# usb_2_0.net
KiCad netlist of a schematic drawn in Altium Designer
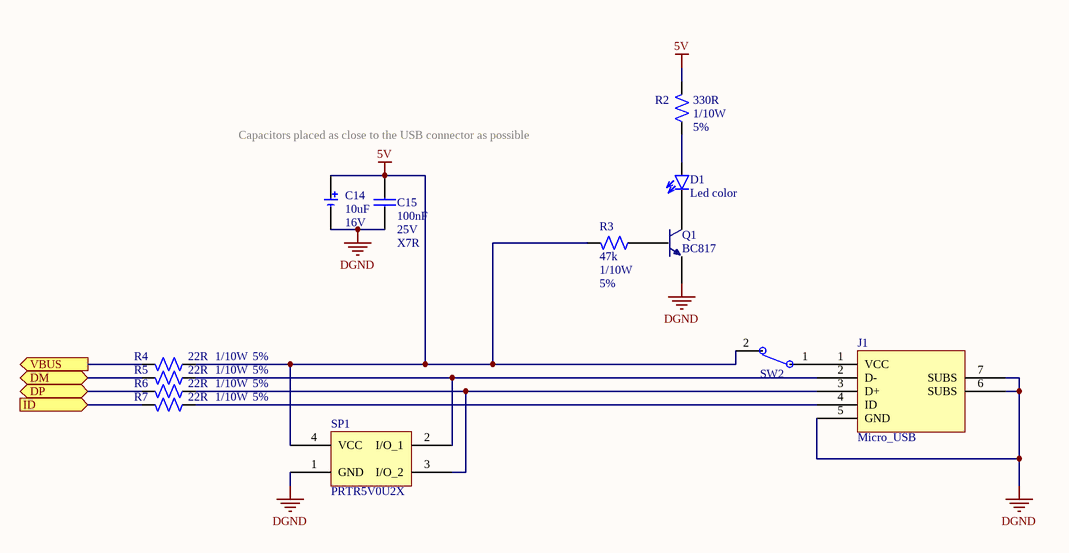
[diagram p0: usb_2_0.SchDoc]

(export (version "E")
  (design (tool "Eeschema 10.0.6"))
  (components
    (comp (ref "C14")
      (value "Capacitor polarizado")
      (footprint "CAP_Electrolytic")
      (fields (field (name "VALOR") "10uF") (field (name "TENSION") "16V"))
      (libsource (lib "Sch_Comunes") (part "Capacitor polarizado"))
    )
    (comp (ref "C15")
      (value "Capacitor")
      (footprint "C0805")
      (description "Capacitor de placas paralelas")
      (fields (field (name "VALOR") "100nF") (field (name "TENSION") "25V") (field (name "TOLERANCIA") "X7R"))
      (libsource (lib "Sch_Comunes") (part "Capacitor"))
    )
    (comp (ref "D1")
      (value "Led color")
      (footprint "Pcb_Comunes_SMD:SMD_0805_Diodo")
      (libsource (lib "sch_comunes") (part "Led"))
    )
    (comp (ref "J1")
      (value "Micro_USB")
      (footprint "USB Type B")
      (description "Conector micro USB tipo B")
      (libsource (lib "Sch_Conectores") (part "Micro_USB"))
    )
    (comp (ref "Q1")
      (value "BC817")
      (footprint "SOT23")
      (description "NPN")
      (libsource (lib "sch_comunes") (part "NPN"))
    )
    (comp (ref "R2")
      (value "Resistor")
      (footprint "R0805")
      (description "Resistencia")
      (fields
        (field (name "VALOR") "330R")
        (field (name "POTENCIA") "1/10W")
        (field (name "TOLERANCIA") "5%")
      )
      (libsource (lib "sch_comunes") (part "Resistor"))
    )
    (comp (ref "R3")
      (value "Resistor")
      (footprint "R0805")
      (description "Resistencia")
      (fields (field (name "VALOR") "47k") (field (name "POTENCIA") "1/10W") (field (name "TOLERANCIA") "5%"))
      (libsource (lib "sch_comunes") (part "Resistor"))
    )
    (comp (ref "R4")
      (value "Resistor")
      (footprint "R0805")
      (description "Resistencia")
      (fields (field (name "VALOR") "22R") (field (name "POTENCIA") "1/10W") (field (name "TOLERANCIA") "5%"))
      (libsource (lib "sch_comunes") (part "Resistor"))
    )
    (comp (ref "R5")
      (value "Resistor")
      (footprint "R0805")
      (description "Resistencia")
      (fields (field (name "VALOR") "22R") (field (name "POTENCIA") "1/10W") (field (name "TOLERANCIA") "5%"))
      (libsource (lib "sch_comunes") (part "Resistor"))
    )
    (comp (ref "R6")
      (value "Resistor")
      (footprint "R0805")
      (description "Resistencia")
      (fields (field (name "VALOR") "22R") (field (name "POTENCIA") "1/10W") (field (name "TOLERANCIA") "5%"))
      (libsource (lib "sch_comunes") (part "Resistor"))
    )
    (comp (ref "R7")
      (value "Resistor")
      (footprint "R0805")
      (description "Resistencia")
      (fields (field (name "VALOR") "22R") (field (name "POTENCIA") "1/10W") (field (name "TOLERANCIA") "5%"))
      (libsource (lib "sch_comunes") (part "Resistor"))
    )
    (comp (ref "SP1")
      (value "PRTR5V0U2X")
      (footprint "SOT143B")
      (description "Double rail-to-rail ESD protection diode")
      (libsource (lib "Sch_Proteccion") (part "Double ESD"))
    )
    (comp (ref "SW2")
      (value "OnOff_SW_SPST")
      (footprint "SPST_TH_SW_Button_90º")
      (libsource (lib "sch_comunes") (part "OnOff_SW_SPST"))
    )
  )
  (nets
    (net (code "1") (name "/DM") (class "Default")
      (node (ref "R5") (pin "2") (pinfunction "2_2") (pintype "passive"))
    )
    (net (code "2") (name "/DP") (class "Default")
      (node (ref "R6") (pin "2") (pinfunction "2_2") (pintype "passive"))
    )
    (net (code "3") (name "/ID") (class "Default")
      (node (ref "R7") (pin "2") (pinfunction "2_2") (pintype "passive"))
    )
    (net (code "4") (name "/VBUS") (class "Default")
      (node (ref "R4") (pin "2") (pinfunction "2_2") (pintype "passive"))
    )
    (net (code "5") (name "5V") (class "Default")
      (node (ref "C14") (pin "1") (pinfunction "1_1") (pintype "passive"))
      (node (ref "C15") (pin "1") (pinfunction "1_1") (pintype "passive"))
      (node (ref "R2") (pin "2") (pinfunction "2_2") (pintype "passive"))
      (node (ref "R3") (pin "2") (pinfunction "2_2") (pintype "passive"))
      (node (ref "R4") (pin "1") (pinfunction "1_1") (pintype "passive"))
      (node (ref "SP1") (pin "4") (pinfunction "VCC_4") (pintype "passive"))
      (node (ref "SW2") (pin "2") (pinfunction "2_2") (pintype "passive"))
    )
    (net (code "6") (name "DGND") (class "Default")
      (node (ref "C14") (pin "2") (pinfunction "2_2") (pintype "passive"))
      (node (ref "C15") (pin "2") (pinfunction "2_2") (pintype "passive"))
      (node (ref "J1") (pin "5") (pinfunction "GND_5") (pintype "passive"))
      (node (ref "J1") (pin "6") (pinfunction "SUBS_6") (pintype "passive"))
      (node (ref "J1") (pin "7") (pinfunction "SUBS_7") (pintype "passive"))
      (node (ref "Q1") (pin "2") (pintype "passive"))
      (node (ref "SP1") (pin "1") (pinfunction "GND_1") (pintype "passive"))
    )
    (net (code "7") (name "Net-(D1-Pad1)") (class "Default")
      (node (ref "D1") (pin "1") (pinfunction "1_1") (pintype "passive"))
      (node (ref "Q1") (pin "3") (pintype "passive"))
    )
    (net (code "8") (name "Net-(D1-Pad2)") (class "Default")
      (node (ref "D1") (pin "2") (pinfunction "2_2") (pintype "passive"))
      (node (ref "R2") (pin "1") (pinfunction "1_1") (pintype "passive"))
    )
    (net (code "9") (name "Net-(J1-D+)") (class "Default")
      (node (ref "J1") (pin "3") (pinfunction "D+_3") (pintype "passive"))
      (node (ref "R6") (pin "1") (pinfunction "1_1") (pintype "passive"))
      (node (ref "SP1") (pin "3") (pinfunction "I/O_2_3") (pintype "passive"))
    )
    (net (code "10") (name "Net-(J1-D-)") (class "Default")
      (node (ref "J1") (pin "2") (pinfunction "D-_2") (pintype "passive"))
      (node (ref "R5") (pin "1") (pinfunction "1_1") (pintype "passive"))
      (node (ref "SP1") (pin "2") (pinfunction "I/O_1_2") (pintype "passive"))
    )
    (net (code "11") (name "Net-(J1-ID)") (class "Default")
      (node (ref "J1") (pin "4") (pinfunction "ID_4") (pintype "passive"))
      (node (ref "R7") (pin "1") (pinfunction "1_1") (pintype "passive"))
    )
    (net (code "12") (name "Net-(J1-VCC)") (class "Default")
      (node (ref "J1") (pin "1") (pinfunction "VCC_1") (pintype "passive"))
      (node (ref "SW2") (pin "1") (pinfunction "1_1") (pintype "passive"))
    )
    (net (code "13") (name "Net-(Q1-Pad1)") (class "Default")
      (node (ref "Q1") (pin "1") (pintype "passive"))
      (node (ref "R3") (pin "1") (pinfunction "1_1") (pintype "passive"))
    )
  )
)
